# Accelrometer.net
KiCad netlist of a schematic drawn in Altium Designer
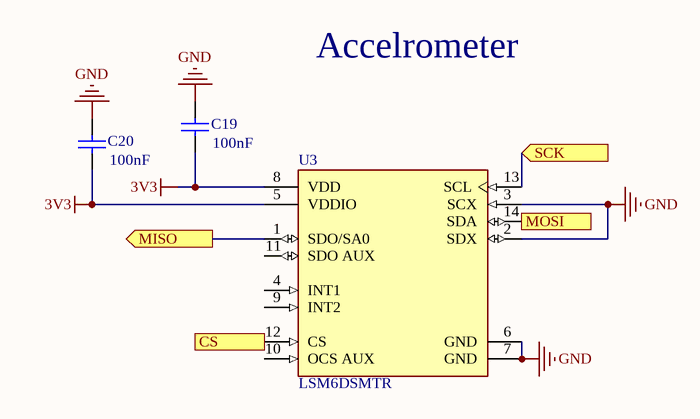
[diagram p0: Accelrometer.SchDoc]

(export (version "E")
  (design (tool "Eeschema 10.0.6"))
  (components
    (comp (ref "C19")
      (value "100nF")
      (footprint "1608[0603]")
      (description "Capacitor")
      (fields (field (name "Comment") "Cap") (field (name "PUBLISHER") "Altium Limited"))
      (libsource (lib "Miscellaneous Devices") (part "Cap"))
    )
    (comp (ref "C20")
      (value "100nF")
      (footprint "1608[0603]")
      (description "Capacitor")
      (fields (field (name "Comment") "Cap") (field (name "PUBLISHER") "Altium Limited"))
      (libsource (lib "Miscellaneous Devices") (part "Cap"))
    )
    (comp (ref "U3")
      (value "LSM6DSMTR")
      (footprint "FP-LGA-14L-DM00249496-MFG")
      (description "IMU ACCEL/GYRO I2C/SPI 14LGA")
      (fields
        (field (name "OCTOPART") "https://octopart.com/lsm6dsmtr-stmicroelectronics-66358194")
        (field (name "MANUFACTURER") "STMicroelectronics")
      )
      (libsource (lib "Altium Content Vault") (part "dd82ae232bae541fa9c740d21cb9072"))
    )
  )
  (nets
    (net (code "1") (name "/CS") (class "Default")
      (node (ref "U3") (pin "12") (pinfunction "CS_12") (pintype "input"))
    )
    (net (code "2") (name "/MISO") (class "Default")
      (node (ref "U3") (pin "1") (pinfunction "SDO/SA0_1") (pintype "bidirectional"))
    )
    (net (code "3") (name "/MOSI") (class "Default")
      (node (ref "U3") (pin "14") (pinfunction "SDA_14") (pintype "bidirectional"))
    )
    (net (code "4") (name "/SCK") (class "Default")
      (node (ref "U3") (pin "13") (pinfunction "SCL_13") (pintype "input"))
    )
    (net (code "5") (name "3V3") (class "Default")
      (node (ref "C19") (pin "2") (pinfunction "2_2") (pintype "passive"))
      (node (ref "C20") (pin "2") (pinfunction "2_2") (pintype "passive"))
      (node (ref "U3") (pin "5") (pinfunction "VDDIO_5") (pintype "power_in"))
      (node (ref "U3") (pin "8") (pinfunction "VDD_8") (pintype "power_in"))
    )
    (net (code "6") (name "GND") (class "Default")
      (node (ref "C19") (pin "1") (pinfunction "1_1") (pintype "passive"))
      (node (ref "C20") (pin "1") (pinfunction "1_1") (pintype "passive"))
      (node (ref "U3") (pin "2") (pinfunction "SDX_2") (pintype "bidirectional"))
      (node (ref "U3") (pin "3") (pinfunction "SCX_3") (pintype "input"))
      (node (ref "U3") (pin "6") (pinfunction "GND_6") (pintype "power_in"))
      (node (ref "U3") (pin "7") (pinfunction "GND_7") (pintype "power_in"))
    )
    (net (code "7") (name "unconnected-(U3-INT1-Pad4)") (class "Default")
      (node (ref "U3") (pin "4") (pinfunction "INT1_4") (pintype "input"))
    )
    (net (code "8") (name "unconnected-(U3-INT2-Pad9)") (class "Default")
      (node (ref "U3") (pin "9") (pinfunction "INT2_9") (pintype "input"))
    )
    (net (code "9") (name "unconnected-(U3-OCS_AUX-Pad10)") (class "Default")
      (node (ref "U3") (pin "10") (pinfunction "OCS_AUX_10") (pintype "input"))
    )
    (net (code "10") (name "unconnected-(U3-SDO_AUX-Pad11)") (class "Default")
      (node (ref "U3") (pin "11") (pinfunction "SDO_AUX_11") (pintype "bidirectional"))
    )
  )
)
